# 19V_Converter.net
KiCad netlist of a schematic drawn in Altium Designer
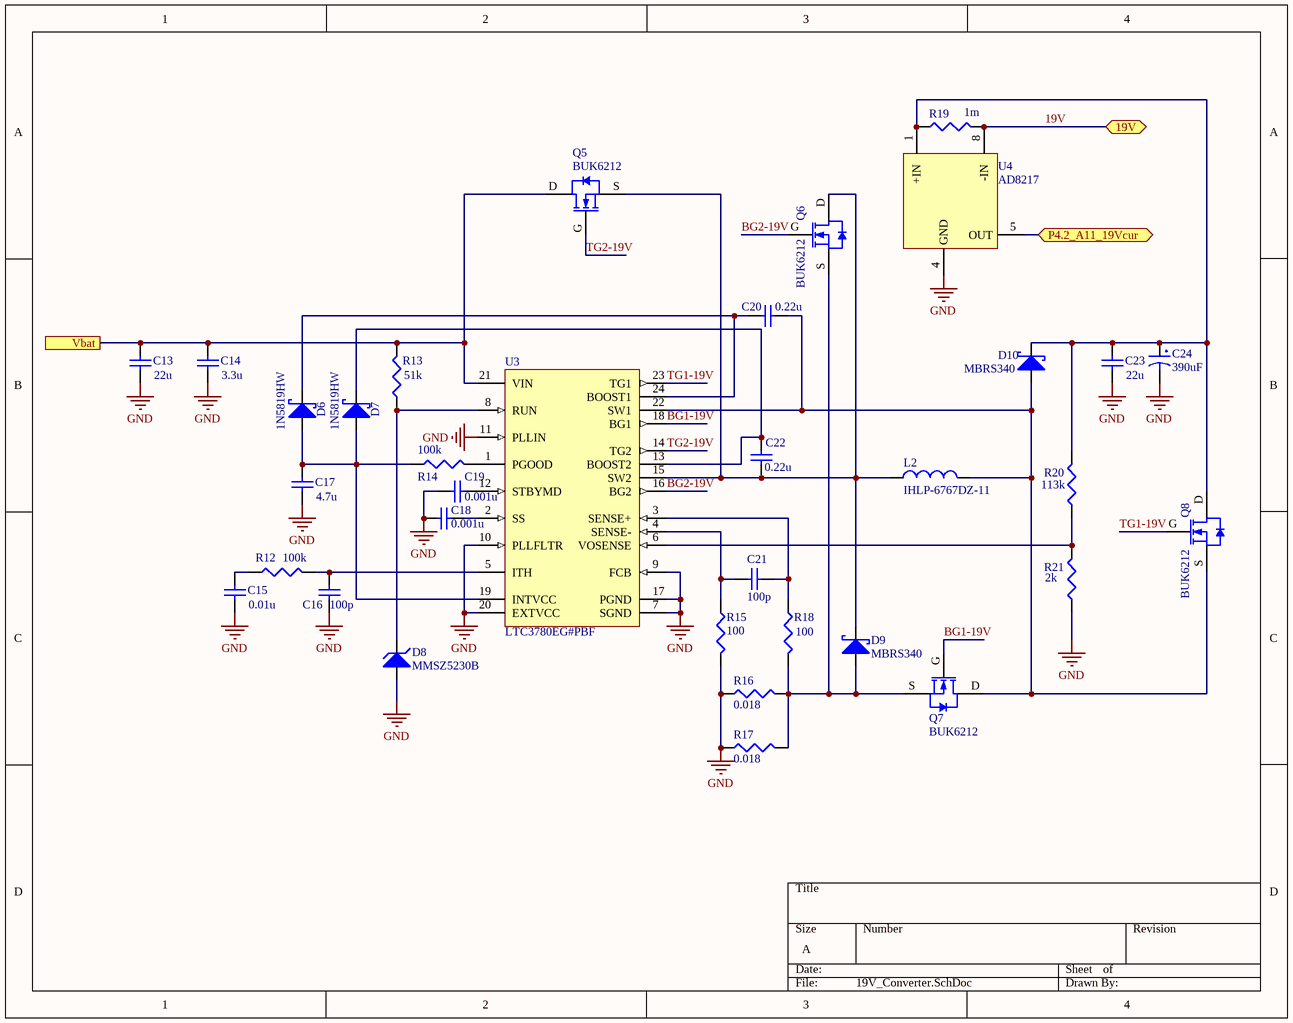
[diagram p0: 19V_Converter.SchDoc]

(export (version "E")
  (design (tool "Eeschema 10.0.6"))
  (components
    (comp (ref "C13")
      (value "22u")
      (footprint "C1206")
      (description "Capacitor (Semiconductor SIM Model)")
      (fields (field (name "Comment") "Cap Semi") (field (name "PUBLISHER") "Altium Limited"))
      (libsource (lib "Miscellaneous Devices") (part "Cap Semi"))
    )
    (comp (ref "C14")
      (value "3.3u")
      (footprint "C1206")
      (description "Capacitor (Semiconductor SIM Model)")
      (fields (field (name "Comment") "Cap Semi") (field (name "PUBLISHER") "Altium Limited"))
      (libsource (lib "Miscellaneous Devices") (part "Cap Semi"))
    )
    (comp (ref "C15")
      (value "0.01u")
      (footprint "C1206")
      (description "Capacitor (Semiconductor SIM Model)")
      (fields (field (name "Comment") "Cap Semi") (field (name "PUBLISHER") "Altium Limited"))
      (libsource (lib "Miscellaneous Devices") (part "Cap Semi"))
    )
    (comp (ref "C16")
      (value "100p")
      (footprint "C1206")
      (description "Capacitor (Semiconductor SIM Model)")
      (fields (field (name "Comment") "Cap Semi") (field (name "PUBLISHER") "Altium Limited"))
      (libsource (lib "Miscellaneous Devices") (part "Cap Semi"))
    )
    (comp (ref "C17")
      (value "4.7u")
      (footprint "C1206")
      (description "Capacitor (Semiconductor SIM Model)")
      (fields (field (name "Comment") "Cap Semi") (field (name "PUBLISHER") "Altium Limited"))
      (libsource (lib "Miscellaneous Devices") (part "Cap Semi"))
    )
    (comp (ref "C18")
      (value "0.001u")
      (footprint "C1206")
      (description "Capacitor (Semiconductor SIM Model)")
      (fields (field (name "Comment") "Cap Semi") (field (name "PUBLISHER") "Altium Limited"))
      (libsource (lib "Miscellaneous Devices") (part "Cap Semi"))
    )
    (comp (ref "C19")
      (value "0.001u")
      (footprint "C1206")
      (description "Capacitor (Semiconductor SIM Model)")
      (fields (field (name "Comment") "Cap Semi") (field (name "PUBLISHER") "Altium Limited"))
      (libsource (lib "Miscellaneous Devices") (part "Cap Semi"))
    )
    (comp (ref "C20")
      (value "0.22u")
      (footprint "C1206")
      (description "Capacitor (Semiconductor SIM Model)")
      (fields (field (name "Comment") "Cap Semi") (field (name "PUBLISHER") "Altium Limited"))
      (libsource (lib "Miscellaneous Devices") (part "Cap Semi"))
    )
    (comp (ref "C21")
      (value "100p")
      (footprint "C1206")
      (description "Capacitor (Semiconductor SIM Model)")
      (fields (field (name "Comment") "Cap Semi") (field (name "PUBLISHER") "Altium Limited"))
      (libsource (lib "Miscellaneous Devices") (part "Cap Semi"))
    )
    (comp (ref "C22")
      (value "0.22u")
      (footprint "C1206")
      (description "Capacitor (Semiconductor SIM Model)")
      (fields (field (name "Comment") "Cap Semi") (field (name "PUBLISHER") "Altium Limited"))
      (libsource (lib "Miscellaneous Devices") (part "Cap Semi"))
    )
    (comp (ref "C23")
      (value "22u")
      (footprint "C1206")
      (description "Capacitor (Semiconductor SIM Model)")
      (fields (field (name "Comment") "Cap Semi") (field (name "PUBLISHER") "Altium Limited"))
      (libsource (lib "Miscellaneous Devices") (part "Cap Semi"))
    )
    (comp (ref "C24")
      (value "390uF")
      (footprint "PCVxxxxxMCLxGS")
      (description "CAP ALUM POLY 390UF 20% 25V SMD")
      (libsource (lib "Power_Embedded_Board_Library") (part "PCV1E391MCL2GS"))
    )
    (comp (ref "D6")
      (value "1N5819HW")
      (footprint "1N58xx")
      (description "1A Schottky Barrier Rectifier Diode")
      (libsource (lib "Power_Embedded_Board_Library") (part "1N58xx"))
    )
    (comp (ref "D7")
      (value "1N5819HW")
      (footprint "1N58xx")
      (description "1A Schottky Barrier Rectifier Diode")
      (libsource (lib "Power_Embedded_Board_Library") (part "1N58xx"))
    )
    (comp (ref "D8")
      (value "MMSZ5230B")
      (footprint "ONSC-SOD-123-2-425-04_V")
      (description "Zener Voltage Regulator, 500 mW, 2-Pin SOD-123, Pb-Free, Tape and Reel")
      (fields (field (name "MANUFACTURER") "On Semiconductor") (field (name "PARTNUMBER") "MMSZ5230BT1G"))
      (libsource (lib "Power_Embedded_Board_Library") (part "MMSZ5230BT1G"))
    )
    (comp (ref "D9")
      (value "MBRS340")
      (footprint "MBRS340")
      (description "Schottky Rectifier")
      (libsource (lib "Power_Embedded_Board_Library") (part "MBRS340"))
    )
    (comp (ref "D10")
      (value "MBRS340")
      (footprint "MBRS340")
      (description "Schottky Rectifier")
      (libsource (lib "Power_Embedded_Board_Library") (part "MBRS340"))
    )
    (comp (ref "L2")
      (value "IHLP-6767DZ-11")
      (footprint "IHLP-6767DZ-11")
      (description "15µH Shielded Molded Inductor 14A 14.4 mOhm Max Nonstandard")
      (libsource (lib "Power_Embedded_Board_Library") (part "IHLP-6767DZ-11"))
    )
    (comp (ref "Q5")
      (value "BUK6212")
      (footprint "NXP-SOT428_M")
      (description "N-Channel TrenchMOS Intermediate Level FET, 40 V, 50 A, 3-Pin SOT428, Tape and Reel")
      (fields
        (field (name "MANUFACTURER") "NXP Semiconductors")
        (field (name "PARTNUMBER") "BUK6212-40C,118")
      )
      (libsource (lib "Power_Embedded_Board_Library") (part "BUK6212"))
    )
    (comp (ref "Q6")
      (value "BUK6212")
      (footprint "NXP-SOT428_M")
      (description "N-Channel TrenchMOS Intermediate Level FET, 40 V, 50 A, 3-Pin SOT428, Tape and Reel")
      (fields
        (field (name "MANUFACTURER") "NXP Semiconductors")
        (field (name "PARTNUMBER") "BUK6212-40C,118")
      )
      (libsource (lib "Power_Embedded_Board_Library") (part "BUK6212"))
    )
    (comp (ref "Q7")
      (value "BUK6212")
      (footprint "NXP-SOT428_M")
      (description "N-Channel TrenchMOS Intermediate Level FET, 40 V, 50 A, 3-Pin SOT428, Tape and Reel")
      (fields
        (field (name "MANUFACTURER") "NXP Semiconductors")
        (field (name "PARTNUMBER") "BUK6212-40C,118")
      )
      (libsource (lib "Power_Embedded_Board_Library") (part "BUK6212"))
    )
    (comp (ref "Q8")
      (value "BUK6212")
      (footprint "NXP-SOT428_M")
      (description "N-Channel TrenchMOS Intermediate Level FET, 40 V, 50 A, 3-Pin SOT428, Tape and Reel")
      (fields
        (field (name "MANUFACTURER") "NXP Semiconductors")
        (field (name "PARTNUMBER") "BUK6212-40C,118")
      )
      (libsource (lib "Power_Embedded_Board_Library") (part "BUK6212"))
    )
    (comp (ref "R12")
      (value "100k")
      (footprint "J1-0603")
      (description "Resistor")
      (fields (field (name "Comment") "Res3") (field (name "PUBLISHER") "Altium Limited"))
      (libsource (lib "Miscellaneous Devices") (part "Res3"))
    )
    (comp (ref "R13")
      (value "51k")
      (footprint "J1-0603")
      (description "Resistor")
      (fields (field (name "Comment") "Res3") (field (name "PUBLISHER") "Altium Limited"))
      (libsource (lib "Miscellaneous Devices") (part "Res3"))
    )
    (comp (ref "R14")
      (value "100k")
      (footprint "J1-0603")
      (description "Resistor")
      (fields (field (name "Comment") "Res3") (field (name "PUBLISHER") "Altium Limited"))
      (libsource (lib "Miscellaneous Devices") (part "Res3"))
    )
    (comp (ref "R15")
      (value "100")
      (footprint "J1-0603")
      (description "Resistor")
      (fields (field (name "Comment") "Res3") (field (name "PUBLISHER") "Altium Limited"))
      (libsource (lib "Miscellaneous Devices") (part "Res3"))
    )
    (comp (ref "R16")
      (value "0.018")
      (footprint "R1206")
      (description "Resistor")
      (fields (field (name "Comment") "Res3") (field (name "PUBLISHER") "Altium Limited"))
      (libsource (lib "Miscellaneous Devices") (part "Res3"))
    )
    (comp (ref "R17")
      (value "0.018")
      (footprint "R1206")
      (description "Resistor")
      (fields (field (name "Comment") "Res3") (field (name "PUBLISHER") "Altium Limited"))
      (libsource (lib "Miscellaneous Devices") (part "Res3"))
    )
    (comp (ref "R18")
      (value "100")
      (footprint "J1-0603")
      (description "Resistor")
      (fields (field (name "Comment") "Res3") (field (name "PUBLISHER") "Altium Limited"))
      (libsource (lib "Miscellaneous Devices") (part "Res3"))
    )
    (comp (ref "R19")
      (value "1m")
      (footprint "14-1210")
      (description "Resistor")
      (fields (field (name "Comment") "Res3") (field (name "PUBLISHER") "Altium Limited"))
      (libsource (lib "Miscellaneous Devices") (part "Res3"))
    )
    (comp (ref "R20")
      (value "113k")
      (footprint "J1-0603")
      (description "Resistor")
      (fields (field (name "Comment") "Res3") (field (name "PUBLISHER") "Altium Limited"))
      (libsource (lib "Miscellaneous Devices") (part "Res3"))
    )
    (comp (ref "R21")
      (value "2k")
      (footprint "J1-0603")
      (description "Resistor")
      (fields (field (name "Comment") "Res3") (field (name "PUBLISHER") "Altium Limited"))
      (libsource (lib "Miscellaneous Devices") (part "Res3"))
    )
    (comp (ref "U3")
      (value "LTC3780EG#PBF")
      (footprint "LT-G-24_L")
      (fields (field (name "MANUFACTURER") "Linear Technology"))
      (libsource (lib "Power_Embedded_Board_Library") (part "LTC3780EG#PBF"))
    )
    (comp (ref "U4")
      (value "AD8217")
      (footprint "AD8217")
      (description "High Resolution, Zero-Drift  Current Shunt Monitor")
      (libsource (lib "Power_Embedded_Board_Library") (part "AD8217"))
    )
  )
  (nets
    (net (code "1") (name "/19V") (class "Default")
      (node (ref "R19") (pin "2") (pinfunction "2_2") (pintype "passive"))
      (node (ref "U4") (pin "8") (pinfunction "-IN_8") (pintype "passive"))
    )
    (net (code "2") (name "/BG1-19V") (class "Default")
      (node (ref "Q7") (pin "G") (pinfunction "G_G") (pintype "passive"))
      (node (ref "U3") (pin "18") (pinfunction "BG1_18") (pintype "output"))
    )
    (net (code "3") (name "/BG2-19V") (class "Default")
      (node (ref "Q6") (pin "G") (pinfunction "G_G") (pintype "passive"))
      (node (ref "U3") (pin "16") (pinfunction "BG2_16") (pintype "output"))
    )
    (net (code "4") (name "/P4.2_A11_19Vcur") (class "Default")
      (node (ref "U4") (pin "5") (pinfunction "OUT_5") (pintype "passive"))
    )
    (net (code "5") (name "/TG1-19V") (class "Default")
      (node (ref "Q8") (pin "G") (pinfunction "G_G") (pintype "passive"))
      (node (ref "U3") (pin "23") (pinfunction "TG1_23") (pintype "output"))
    )
    (net (code "6") (name "/TG2-19V") (class "Default")
      (node (ref "Q5") (pin "G") (pinfunction "G_G") (pintype "passive"))
      (node (ref "U3") (pin "14") (pinfunction "TG2_14") (pintype "output"))
    )
    (net (code "7") (name "/Vbat") (class "Default")
      (node (ref "C13") (pin "2") (pinfunction "2_2") (pintype "passive"))
      (node (ref "C14") (pin "2") (pinfunction "2_2") (pintype "passive"))
      (node (ref "Q5") (pin "D") (pinfunction "D_D") (pintype "passive"))
      (node (ref "R13") (pin "2") (pinfunction "2_2") (pintype "passive"))
      (node (ref "U3") (pin "21") (pinfunction "VIN_21") (pintype "power_in"))
    )
    (net (code "8") (name "GND") (class "Default")
      (node (ref "C13") (pin "1") (pinfunction "1_1") (pintype "passive"))
      (node (ref "C14") (pin "1") (pinfunction "1_1") (pintype "passive"))
      (node (ref "C15") (pin "1") (pinfunction "1_1") (pintype "passive"))
      (node (ref "C16") (pin "1") (pinfunction "1_1") (pintype "passive"))
      (node (ref "C17") (pin "1") (pinfunction "1_1") (pintype "passive"))
      (node (ref "C18") (pin "1") (pinfunction "1_1") (pintype "passive"))
      (node (ref "C19") (pin "1") (pinfunction "1_1") (pintype "passive"))
      (node (ref "C23") (pin "1") (pinfunction "1_1") (pintype "passive"))
      (node (ref "C24") (pin "2") (pinfunction "2_2") (pintype "passive"))
      (node (ref "D8") (pin "2") (pinfunction "A_2") (pintype "passive"))
      (node (ref "R15") (pin "2") (pinfunction "2_2") (pintype "passive"))
      (node (ref "R16") (pin "1") (pinfunction "1_1") (pintype "passive"))
      (node (ref "R17") (pin "1") (pinfunction "1_1") (pintype "passive"))
      (node (ref "R21") (pin "1") (pinfunction "1_1") (pintype "passive"))
      (node (ref "U3") (pin "10") (pinfunction "PLLFLTR_10") (pintype "input"))
      (node (ref "U3") (pin "11") (pinfunction "PLLIN_11") (pintype "input"))
      (node (ref "U3") (pin "17") (pinfunction "PGND_17") (pintype "power_in"))
      (node (ref "U3") (pin "20") (pinfunction "EXTVCC_20") (pintype "power_in"))
      (node (ref "U3") (pin "7") (pinfunction "SGND_7") (pintype "power_in"))
      (node (ref "U3") (pin "9") (pinfunction "FCB_9") (pintype "input"))
      (node (ref "U4") (pin "4") (pinfunction "GND_4") (pintype "passive"))
    )
    (net (code "9") (name "Net-(C15-Pad2)") (class "Default")
      (node (ref "C15") (pin "2") (pinfunction "2_2") (pintype "passive"))
      (node (ref "R12") (pin "1") (pinfunction "1_1") (pintype "passive"))
    )
    (net (code "10") (name "Net-(D6-Anode)") (class "Default")
      (node (ref "C17") (pin "2") (pinfunction "2_2") (pintype "passive"))
      (node (ref "D6") (pin "A") (pinfunction "Anode_A") (pintype "passive"))
      (node (ref "D7") (pin "A") (pinfunction "Anode_A") (pintype "passive"))
      (node (ref "R14") (pin "1") (pinfunction "1_1") (pintype "passive"))
      (node (ref "U3") (pin "19") (pinfunction "INTVCC_19") (pintype "power_in"))
    )
    (net (code "11") (name "Net-(D6-Cathode)") (class "Default")
      (node (ref "C20") (pin "2") (pinfunction "2_2") (pintype "passive"))
      (node (ref "D6") (pin "K") (pinfunction "Cathode_K") (pintype "passive"))
      (node (ref "U3") (pin "24") (pinfunction "BOOST1_24") (pintype "passive"))
    )
    (net (code "12") (name "Net-(D7-Cathode)") (class "Default")
      (node (ref "C22") (pin "2") (pinfunction "2_2") (pintype "passive"))
      (node (ref "D7") (pin "K") (pinfunction "Cathode_K") (pintype "passive"))
      (node (ref "U3") (pin "13") (pinfunction "BOOST2_13") (pintype "passive"))
    )
    (net (code "13") (name "Net-(D8-K)") (class "Default")
      (node (ref "D8") (pin "1") (pinfunction "K_1") (pintype "passive"))
      (node (ref "R13") (pin "1") (pinfunction "1_1") (pintype "passive"))
      (node (ref "U3") (pin "8") (pinfunction "RUN_8") (pintype "input"))
    )
    (net (code "14") (name "Net-(D9-Anode)") (class "Default")
      (node (ref "D9") (pin "A") (pinfunction "Anode_A") (pintype "passive"))
      (node (ref "Q6") (pin "S") (pinfunction "S_S") (pintype "passive"))
      (node (ref "Q7") (pin "S") (pinfunction "S_S") (pintype "passive"))
      (node (ref "R16") (pin "2") (pinfunction "2_2") (pintype "passive"))
      (node (ref "R17") (pin "2") (pinfunction "2_2") (pintype "passive"))
      (node (ref "R18") (pin "2") (pinfunction "2_2") (pintype "passive"))
    )
    (net (code "15") (name "Net-(D9-Cathode)") (class "Default")
      (node (ref "C22") (pin "1") (pinfunction "1_1") (pintype "passive"))
      (node (ref "D9") (pin "K") (pinfunction "Cathode_K") (pintype "passive"))
      (node (ref "L2") (pin "1") (pinfunction "1_1") (pintype "passive"))
      (node (ref "Q5") (pin "S") (pinfunction "S_S") (pintype "passive"))
      (node (ref "Q6") (pin "D") (pinfunction "D_D") (pintype "passive"))
      (node (ref "U3") (pin "15") (pinfunction "SW2_15") (pintype "passive"))
    )
    (net (code "16") (name "Net-(D10-Anode)") (class "Default")
      (node (ref "C20") (pin "1") (pinfunction "1_1") (pintype "passive"))
      (node (ref "D10") (pin "A") (pinfunction "Anode_A") (pintype "passive"))
      (node (ref "L2") (pin "2") (pinfunction "2_2") (pintype "passive"))
      (node (ref "Q7") (pin "D") (pinfunction "D_D") (pintype "passive"))
      (node (ref "Q8") (pin "S") (pinfunction "S_S") (pintype "passive"))
      (node (ref "U3") (pin "22") (pinfunction "SW1_22") (pintype "passive"))
    )
    (net (code "17") (name "Net-(D10-Cathode)") (class "Default")
      (node (ref "C23") (pin "2") (pinfunction "2_2") (pintype "passive"))
      (node (ref "C24") (pin "1") (pinfunction "1_1") (pintype "passive"))
      (node (ref "D10") (pin "K") (pinfunction "Cathode_K") (pintype "passive"))
      (node (ref "Q8") (pin "D") (pinfunction "D_D") (pintype "passive"))
      (node (ref "R19") (pin "1") (pinfunction "1_1") (pintype "passive"))
      (node (ref "R20") (pin "2") (pinfunction "2_2") (pintype "passive"))
      (node (ref "U4") (pin "1") (pinfunction "+IN_1") (pintype "passive"))
    )
    (net (code "18") (name "Net-(U3-ITH)") (class "Default")
      (node (ref "C16") (pin "2") (pinfunction "2_2") (pintype "passive"))
      (node (ref "R12") (pin "2") (pinfunction "2_2") (pintype "passive"))
      (node (ref "U3") (pin "5") (pinfunction "ITH_5") (pintype "passive"))
    )
    (net (code "19") (name "Net-(U3-PGOOD)") (class "Default")
      (node (ref "R14") (pin "2") (pinfunction "2_2") (pintype "passive"))
      (node (ref "U3") (pin "1") (pinfunction "PGOOD_1") (pintype "open_collector"))
    )
    (net (code "20") (name "Net-(U3-SENSE+)") (class "Default")
      (node (ref "C21") (pin "2") (pinfunction "2_2") (pintype "passive"))
      (node (ref "R18") (pin "1") (pinfunction "1_1") (pintype "passive"))
      (node (ref "U3") (pin "3") (pinfunction "SENSE+_3") (pintype "input"))
    )
    (net (code "21") (name "Net-(U3-SENSE-)") (class "Default")
      (node (ref "C21") (pin "1") (pinfunction "1_1") (pintype "passive"))
      (node (ref "R15") (pin "1") (pinfunction "1_1") (pintype "passive"))
      (node (ref "U3") (pin "4") (pinfunction "SENSE-_4") (pintype "input"))
    )
    (net (code "22") (name "Net-(U3-SS)") (class "Default")
      (node (ref "C18") (pin "2") (pinfunction "2_2") (pintype "passive"))
      (node (ref "U3") (pin "2") (pinfunction "SS_2") (pintype "input"))
    )
    (net (code "23") (name "Net-(U3-STBYMD)") (class "Default")
      (node (ref "C19") (pin "2") (pinfunction "2_2") (pintype "passive"))
      (node (ref "U3") (pin "12") (pinfunction "STBYMD_12") (pintype "input"))
    )
    (net (code "24") (name "Net-(U3-VOSENSE)") (class "Default")
      (node (ref "R20") (pin "1") (pinfunction "1_1") (pintype "passive"))
      (node (ref "R21") (pin "2") (pinfunction "2_2") (pintype "passive"))
      (node (ref "U3") (pin "6") (pinfunction "VOSENSE_6") (pintype "input"))
    )
  )
)
